# eia-485-bus.net
KiCad netlist of a schematic drawn in EAGLE
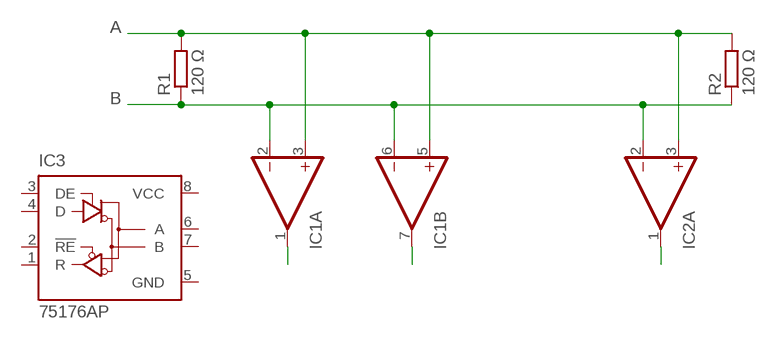
[diagram p0: schematic, sheet 1]

(export (version "E")
  (design (tool "Eeschema 10.0.6"))
  (components
    (comp (ref "IC1")
      (value "2AMP_P8+4N")
      (footprint "eagle-import:DIL08")
      (libsource (lib "eagle-import") (part "2AMP_P8+4N"))
    )
    (comp (ref "IC2")
      (value "2AMP_P8+4N")
      (footprint "eagle-import:DIL08")
      (libsource (lib "eagle-import") (part "2AMP_P8+4N"))
    )
    (comp (ref "IC3")
      (value "75176AP")
      (footprint "eagle-import:DIL08")
      (libsource (lib "eagle-import") (part "75176AP"))
    )
    (comp (ref "R1")
      (value "120 Ω")
      (footprint "eagle-import:0204_7")
      (libsource (lib "eagle-import") (part "R-EU_0204/7"))
    )
    (comp (ref "R2")
      (value "120 Ω")
      (footprint "eagle-import:0204_7")
      (libsource (lib "eagle-import") (part "R-EU_0204/7"))
    )
  )
  (nets
    (net (code "1") (name "/A") (class "Default")
      (node (ref "IC1") (pin "3") (pinfunction "+IN_3") (pintype "input"))
      (node (ref "IC1") (pin "5") (pinfunction "+IN_5") (pintype "input"))
      (node (ref "IC2") (pin "3") (pinfunction "+IN_3") (pintype "input"))
      (node (ref "R1") (pin "2") (pinfunction "2_2") (pintype "passive"))
      (node (ref "R2") (pin "2") (pinfunction "2_2") (pintype "passive"))
    )
    (net (code "2") (name "/B") (class "Default")
      (node (ref "IC1") (pin "2") (pinfunction "-IN_2") (pintype "input"))
      (node (ref "IC1") (pin "6") (pinfunction "-IN_6") (pintype "input"))
      (node (ref "IC2") (pin "2") (pinfunction "-IN_2") (pintype "input"))
      (node (ref "R1") (pin "1") (pinfunction "1_1") (pintype "passive"))
      (node (ref "R2") (pin "1") (pinfunction "1_1") (pintype "passive"))
    )
    (net (code "3") (name "/GND") (class "Default")
      (node (ref "IC3") (pin "5") (pinfunction "GND_5") (pintype "power_in"))
    )
    (net (code "4") (name "/VCC") (class "Default")
      (node (ref "IC3") (pin "8") (pinfunction "VCC_8") (pintype "power_in"))
    )
    (net (code "5") (name "unconnected-(IC1A-OUT-Pad1)") (class "Default")
      (node (ref "IC1") (pin "1") (pinfunction "OUT_1") (pintype "output"))
    )
    (net (code "6") (name "unconnected-(IC1B-OUT-Pad7)") (class "Default")
      (node (ref "IC1") (pin "7") (pinfunction "OUT_7") (pintype "output"))
    )
    (net (code "7") (name "unconnected-(IC2A-OUT-Pad1)") (class "Default")
      (node (ref "IC2") (pin "1") (pinfunction "OUT_1") (pintype "output"))
    )
    (net (code "8") (name "unconnected-(IC3-A-Pad6)") (class "Default")
      (node (ref "IC3") (pin "6") (pinfunction "A_6") (pintype "output"))
    )
    (net (code "9") (name "unconnected-(IC3-B-Pad7)") (class "Default")
      (node (ref "IC3") (pin "7") (pinfunction "B_7") (pintype "output"))
    )
    (net (code "10") (name "unconnected-(IC3-D-Pad4)") (class "Default")
      (node (ref "IC3") (pin "4") (pinfunction "D_4") (pintype "input"))
    )
    (net (code "11") (name "unconnected-(IC3-DE-Pad3)") (class "Default")
      (node (ref "IC3") (pin "3") (pinfunction "DE_3") (pintype "input"))
    )
    (net (code "12") (name "unconnected-(IC3-R-Pad1)") (class "Default")
      (node (ref "IC3") (pin "1") (pinfunction "R_1") (pintype "input"))
    )
    (net (code "13") (name "unconnected-(IC3-~{RE}-Pad2)") (class "Default")
      (node (ref "IC3") (pin "2") (pinfunction "~{RE}_2") (pintype "input"))
    )
  )
)
